# LED.net
KiCad netlist of a schematic drawn in Altium Designer
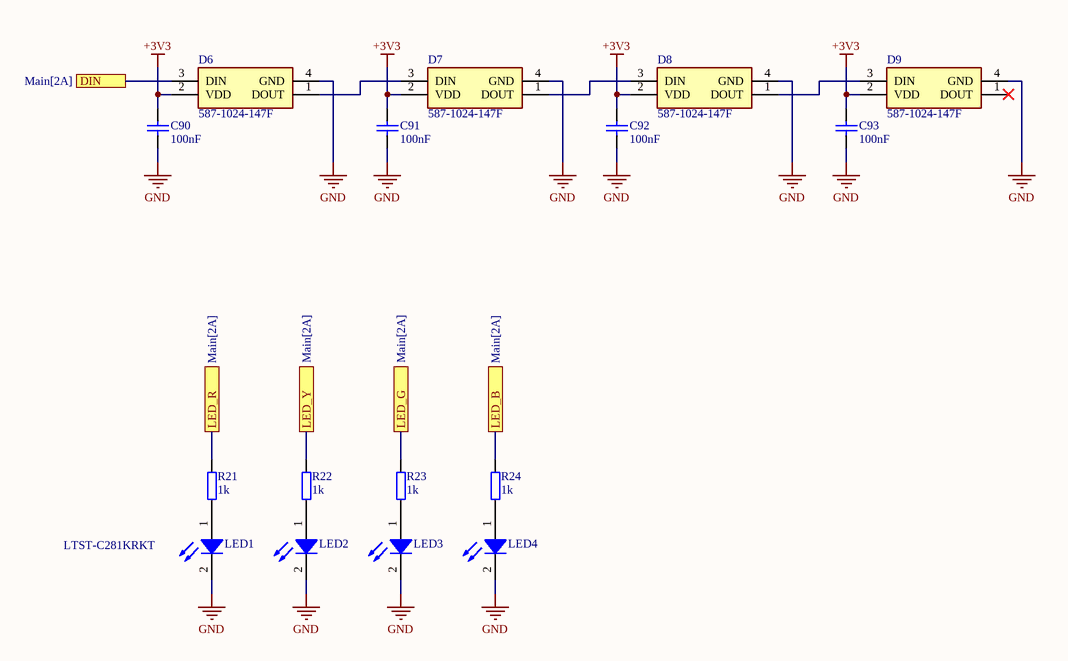
[diagram p0: LED.SchDoc]

(export (version "E")
  (design (tool "Eeschema 10.0.6"))
  (components
    (comp (ref "C90")
      (value "100nF")
      (footprint "CAP0402")
      (fields
        (field (name "VOLTAGE") "50V")
        (field (name "MANUFACTURER_PART_NUMBER") "GRM155R71H104ME14D")
        (field (name "Comment") "Cap0402")
      )
      (libsource (lib "capacitorsSMD") (part "Cap0402"))
    )
    (comp (ref "C91")
      (value "100nF")
      (footprint "CAP0402")
      (fields
        (field (name "VOLTAGE") "50V")
        (field (name "MANUFACTURER_PART_NUMBER") "GRM155R71H104ME14D")
        (field (name "Comment") "Cap0402")
      )
      (libsource (lib "capacitorsSMD") (part "Cap0402"))
    )
    (comp (ref "C92")
      (value "100nF")
      (footprint "CAP0402")
      (fields
        (field (name "VOLTAGE") "50V")
        (field (name "MANUFACTURER_PART_NUMBER") "GRM155R71H104ME14D")
        (field (name "Comment") "Cap0402")
      )
      (libsource (lib "capacitorsSMD") (part "Cap0402"))
    )
    (comp (ref "C93")
      (value "100nF")
      (footprint "CAP0402")
      (fields
        (field (name "VOLTAGE") "50V")
        (field (name "MANUFACTURER_PART_NUMBER") "GRM155R71H104ME14D")
        (field (name "Comment") "Cap0402")
      )
      (libsource (lib "capacitorsSMD") (part "Cap0402"))
    )
    (comp (ref "D6")
      (value "587-1024-147F")
      (footprint "SamacSys:5871024147F")
      (description "LED")
      (libsource (lib "*") (part "587-1024-147F"))
    )
    (comp (ref "D7")
      (value "587-1024-147F")
      (footprint "SamacSys:5871024147F")
      (description "LED")
      (libsource (lib "*") (part "587-1024-147F"))
    )
    (comp (ref "D8")
      (value "587-1024-147F")
      (footprint "SamacSys:5871024147F")
      (description "LED")
      (libsource (lib "*") (part "587-1024-147F"))
    )
    (comp (ref "D9")
      (value "587-1024-147F")
      (footprint "SamacSys:5871024147F")
      (description "LED")
      (libsource (lib "*") (part "587-1024-147F"))
    )
    (comp (ref "LED1")
      (value "LTST-C281KRKT")
      (footprint "SamacSys:LTSTC281KRKT")
      (description "LED (Multiple)")
      (fields (field (name "MOUSER PART NUMBER") "859-LTST-C281KRKT"))
      (libsource (lib "SamacSys") (part "LTST-C281KRKT"))
    )
    (comp (ref "LED2")
      (value "LTST-C281KSKT")
      (footprint "SamacSys:LTSTC281KRKT")
      (description "LED (Multiple)")
      (fields
        (field (name "MANUFACTURER_PART_NUMBER") "LTST-C281KRKT")
        (field (name "MOUSER PART NUMBER") "859-LTST-C281KRKT")
      )
      (libsource (lib "SamacSys") (part "LTST-C281KRKT"))
    )
    (comp (ref "LED3")
      (value "LTST-C281KGKT")
      (footprint "SamacSys:LTSTC281KRKT")
      (description "LED (Multiple)")
      (fields
        (field (name "MANUFACTURER_PART_NUMBER") "LTST-C281KRKT")
        (field (name "MOUSER PART NUMBER") "859-LTST-C281KRKT")
      )
      (libsource (lib "SamacSys") (part "LTST-C281KRKT"))
    )
    (comp (ref "LED4")
      (value "LTST-C281KBKT")
      (footprint "SamacSys:LTSTC281KRKT")
      (description "LED (Multiple)")
      (fields
        (field (name "MANUFACTURER_PART_NUMBER") "LTST-C281KRKT")
        (field (name "MOUSER PART NUMBER") "859-LTST-C281KRKT")
      )
      (libsource (lib "SamacSys") (part "LTST-C281KRKT"))
    )
    (comp (ref "R21")
      (value "1k")
      (footprint "RES0402")
      (fields (field (name "MANUFACTURER_PART_NUMBER") "RC0402DR-071KL") (field (name "Comment") "Res0402"))
      (libsource (lib "resistorSMD") (part "Res0402"))
    )
    (comp (ref "R22")
      (value "1k")
      (footprint "RES0402")
      (fields (field (name "MANUFACTURER_PART_NUMBER") "RC0402DR-071KL") (field (name "Comment") "Res0402"))
      (libsource (lib "resistorSMD") (part "Res0402"))
    )
    (comp (ref "R23")
      (value "1k")
      (footprint "RES0402")
      (fields (field (name "MANUFACTURER_PART_NUMBER") "RC0402DR-071KL") (field (name "Comment") "Res0402"))
      (libsource (lib "resistorSMD") (part "Res0402"))
    )
    (comp (ref "R24")
      (value "1k")
      (footprint "RES0402")
      (fields (field (name "MANUFACTURER_PART_NUMBER") "RC0402DR-071KL") (field (name "Comment") "Res0402"))
      (libsource (lib "resistorSMD") (part "Res0402"))
    )
  )
  (nets
    (net (code "1") (name "+3V3") (class "Default")
      (node (ref "C90") (pin "2") (pinfunction "2_2") (pintype "passive"))
      (node (ref "C91") (pin "2") (pinfunction "2_2") (pintype "passive"))
      (node (ref "C92") (pin "2") (pinfunction "2_2") (pintype "passive"))
      (node (ref "C93") (pin "2") (pinfunction "2_2") (pintype "passive"))
      (node (ref "D6") (pin "2") (pinfunction "VDD_2") (pintype "passive"))
      (node (ref "D7") (pin "2") (pinfunction "VDD_2") (pintype "passive"))
      (node (ref "D8") (pin "2") (pinfunction "VDD_2") (pintype "passive"))
      (node (ref "D9") (pin "2") (pinfunction "VDD_2") (pintype "passive"))
    )
    (net (code "2") (name "/DIN") (class "Default")
      (node (ref "D6") (pin "3") (pinfunction "DIN_3") (pintype "passive"))
    )
    (net (code "3") (name "/LED_B") (class "Default")
      (node (ref "R24") (pin "1") (pinfunction "1_1") (pintype "passive"))
    )
    (net (code "4") (name "/LED_G") (class "Default")
      (node (ref "R23") (pin "1") (pinfunction "1_1") (pintype "passive"))
    )
    (net (code "5") (name "/LED_R") (class "Default")
      (node (ref "R21") (pin "1") (pinfunction "1_1") (pintype "passive"))
    )
    (net (code "6") (name "/LED_Y") (class "Default")
      (node (ref "R22") (pin "1") (pinfunction "1_1") (pintype "passive"))
    )
    (net (code "7") (name "GND") (class "Default")
      (node (ref "C90") (pin "1") (pinfunction "1_1") (pintype "passive"))
      (node (ref "C91") (pin "1") (pinfunction "1_1") (pintype "passive"))
      (node (ref "C92") (pin "1") (pinfunction "1_1") (pintype "passive"))
      (node (ref "C93") (pin "1") (pinfunction "1_1") (pintype "passive"))
      (node (ref "D6") (pin "4") (pinfunction "GND_4") (pintype "passive"))
      (node (ref "D7") (pin "4") (pinfunction "GND_4") (pintype "passive"))
      (node (ref "D8") (pin "4") (pinfunction "GND_4") (pintype "passive"))
      (node (ref "D9") (pin "4") (pinfunction "GND_4") (pintype "passive"))
      (node (ref "LED1") (pin "2") (pinfunction "A_2") (pintype "passive"))
      (node (ref "LED2") (pin "2") (pinfunction "A_2") (pintype "passive"))
      (node (ref "LED3") (pin "2") (pinfunction "A_2") (pintype "passive"))
      (node (ref "LED4") (pin "2") (pinfunction "A_2") (pintype "passive"))
    )
    (net (code "8") (name "Net-(D6-DOUT)") (class "Default")
      (node (ref "D6") (pin "1") (pinfunction "DOUT_1") (pintype "passive"))
      (node (ref "D7") (pin "3") (pinfunction "DIN_3") (pintype "passive"))
    )
    (net (code "9") (name "Net-(D7-DOUT)") (class "Default")
      (node (ref "D7") (pin "1") (pinfunction "DOUT_1") (pintype "passive"))
      (node (ref "D8") (pin "3") (pinfunction "DIN_3") (pintype "passive"))
    )
    (net (code "10") (name "Net-(D8-DOUT)") (class "Default")
      (node (ref "D8") (pin "1") (pinfunction "DOUT_1") (pintype "passive"))
      (node (ref "D9") (pin "3") (pinfunction "DIN_3") (pintype "passive"))
    )
    (net (code "11") (name "Net-(LED1-K)") (class "Default")
      (node (ref "LED1") (pin "1") (pinfunction "K_1") (pintype "passive"))
      (node (ref "R21") (pin "2") (pinfunction "2_2") (pintype "passive"))
    )
    (net (code "12") (name "Net-(LED2-K)") (class "Default")
      (node (ref "LED2") (pin "1") (pinfunction "K_1") (pintype "passive"))
      (node (ref "R22") (pin "2") (pinfunction "2_2") (pintype "passive"))
    )
    (net (code "13") (name "Net-(LED3-K)") (class "Default")
      (node (ref "LED3") (pin "1") (pinfunction "K_1") (pintype "passive"))
      (node (ref "R23") (pin "2") (pinfunction "2_2") (pintype "passive"))
    )
    (net (code "14") (name "Net-(LED4-K)") (class "Default")
      (node (ref "LED4") (pin "1") (pinfunction "K_1") (pintype "passive"))
      (node (ref "R24") (pin "2") (pinfunction "2_2") (pintype "passive"))
    )
    (net (code "15") (name "unconnected-(D9-DOUT-Pad1)") (class "Default")
      (node (ref "D9") (pin "1") (pinfunction "DOUT_1") (pintype "passive+no_connect"))
    )
  )
)
